# lixie_usb.net
KiCad netlist of a schematic drawn in EAGLE
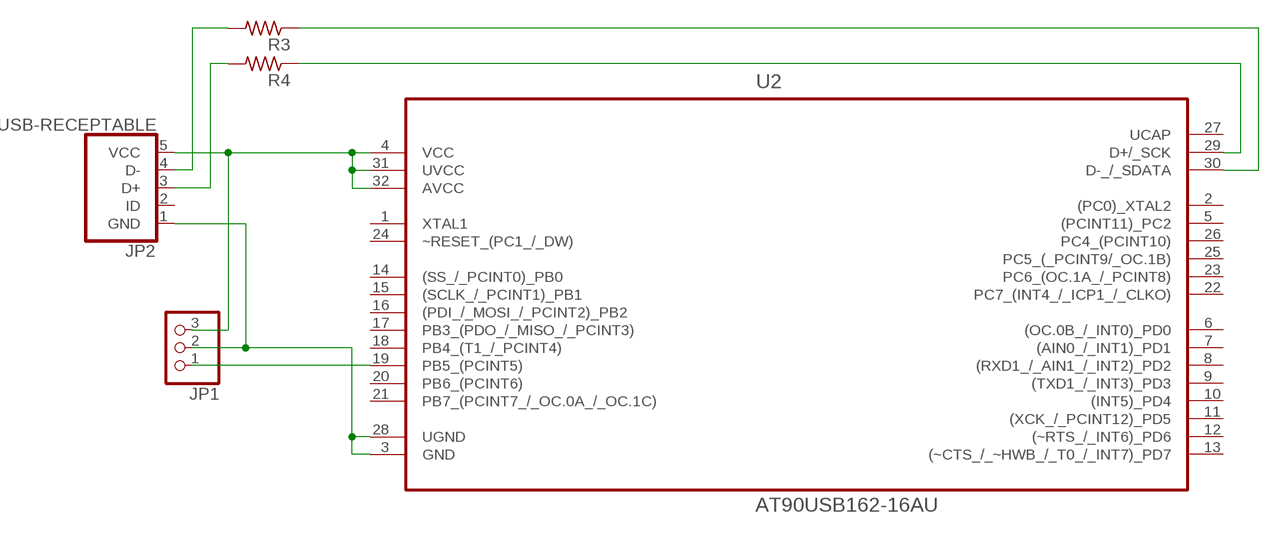
[diagram p0: schematic, sheet 1]

(export (version "E")
  (design (tool "Eeschema 10.0.6"))
  (components
    (comp (ref "JP1")
      (value "PINHD-1X3")
      (footprint "eagle-import:1X03")
      (libsource (lib "eagle-import") (part "PINHD-1X3"))
    )
    (comp (ref "JP2")
      (value "USB-RECEPTABLE")
      (footprint "eagle-import:FCI-10103594-0001LF")
      (libsource (lib "eagle-import") (part "USB-RECEPTABLE"))
    )
    (comp (ref "R3")
      (value "R-US_R0805")
      (footprint "eagle-import:R0805")
      (libsource (lib "eagle-import") (part "R-US_R0805"))
    )
    (comp (ref "R4")
      (value "R-US_R0805")
      (footprint "eagle-import:R0805")
      (libsource (lib "eagle-import") (part "R-US_R0805"))
    )
    (comp (ref "U2")
      (value "AT90USB162-16AU")
      (footprint "eagle-import:QFP80P900X900X120-32N")
      (libsource (lib "eagle-import") (part "AT90USB162-16AU"))
    )
  )
  (nets
    (net (code "1") (name "Net-(JP2-D+)") (class "Default")
      (node (ref "JP2") (pin "3") (pinfunction "D+_3") (pintype "bidirectional"))
      (node (ref "R4") (pin "2") (pinfunction "2_2") (pintype "passive"))
    )
    (net (code "2") (name "Net-(JP2-D-)") (class "Default")
      (node (ref "JP2") (pin "4") (pinfunction "D-_4") (pintype "bidirectional"))
      (node (ref "R3") (pin "2") (pinfunction "2_2") (pintype "passive"))
    )
    (net (code "3") (name "Net-(JP2-GND)") (class "Default")
      (node (ref "JP1") (pin "2") (pinfunction "2_2") (pintype "passive"))
      (node (ref "JP2") (pin "1") (pinfunction "GND_1") (pintype "bidirectional"))
      (node (ref "U2") (pin "28") (pinfunction "UGND_28") (pintype "passive"))
      (node (ref "U2") (pin "3") (pinfunction "GND_3") (pintype "passive"))
    )
    (net (code "4") (name "Net-(JP2-VCC)") (class "Default")
      (node (ref "JP1") (pin "3") (pinfunction "3_3") (pintype "passive"))
      (node (ref "JP2") (pin "5") (pinfunction "VCC_5") (pintype "bidirectional"))
      (node (ref "U2") (pin "31") (pinfunction "UVCC_31") (pintype "power_in"))
      (node (ref "U2") (pin "32") (pinfunction "AVCC_32") (pintype "power_in"))
      (node (ref "U2") (pin "4") (pinfunction "VCC_4") (pintype "power_in"))
    )
    (net (code "5") (name "Net-(U2-D+{slash}_SCK)") (class "Default")
      (node (ref "R4") (pin "1") (pinfunction "1_1") (pintype "passive"))
      (node (ref "U2") (pin "29") (pinfunction "D+/_SCK_29") (pintype "bidirectional"))
    )
    (net (code "6") (name "Net-(U2-D-_{slash}_SDATA)") (class "Default")
      (node (ref "R3") (pin "1") (pinfunction "1_1") (pintype "passive"))
      (node (ref "U2") (pin "30") (pinfunction "D-_/_SDATA_30") (pintype "bidirectional"))
    )
    (net (code "7") (name "Net-(U2-PB5_(PCINT5))") (class "Default")
      (node (ref "JP1") (pin "1") (pinfunction "1_1") (pintype "passive"))
      (node (ref "U2") (pin "19") (pinfunction "PB5_(PCINT5)_19") (pintype "bidirectional"))
    )
    (net (code "8") (name "unconnected-(JP2-ID-Pad2)") (class "Default")
      (node (ref "JP2") (pin "2") (pinfunction "ID_2") (pintype "bidirectional"))
    )
    (net (code "9") (name "unconnected-(U2-(AIN0_{slash}_INT1)_PD1-Pad7)") (class "Default")
      (node (ref "U2") (pin "7") (pinfunction "(AIN0_/_INT1)_PD1_7") (pintype "bidirectional"))
    )
    (net (code "10") (name "unconnected-(U2-(INT5)_PD4-Pad10)") (class "Default")
      (node (ref "U2") (pin "10") (pinfunction "(INT5)_PD4_10") (pintype "bidirectional"))
    )
    (net (code "11") (name "unconnected-(U2-(OC.0B_{slash}_INT0)_PD0-Pad6)") (class "Default")
      (node (ref "U2") (pin "6") (pinfunction "(OC.0B_/_INT0)_PD0_6") (pintype "bidirectional"))
    )
    (net (code "12") (name "unconnected-(U2-(PC0)_XTAL2-Pad2)") (class "Default")
      (node (ref "U2") (pin "2") (pinfunction "(PC0)_XTAL2_2") (pintype "bidirectional"))
    )
    (net (code "13") (name "unconnected-(U2-(PCINT11)_PC2-Pad5)") (class "Default")
      (node (ref "U2") (pin "5") (pinfunction "(PCINT11)_PC2_5") (pintype "bidirectional"))
    )
    (net (code "14") (name "unconnected-(U2-(PDI_{slash}_MOSI_{slash}_PCINT2)_PB2-Pad16)") (class "Default")
      (node (ref "U2") (pin "16") (pinfunction "(PDI_/_MOSI_/_PCINT2)_PB2_16") (pintype "bidirectional"))
    )
    (net (code "15") (name "unconnected-(U2-(RXD1_{slash}_AIN1_{slash}_INT2)_PD2-Pad8)") (class "Default")
      (node (ref "U2") (pin "8") (pinfunction "(RXD1_/_AIN1_/_INT2)_PD2_8") (pintype "bidirectional"))
    )
    (net (code "16") (name "unconnected-(U2-(SCLK_{slash}_PCINT1)_PB1-Pad15)") (class "Default")
      (node (ref "U2") (pin "15") (pinfunction "(SCLK_/_PCINT1)_PB1_15") (pintype "bidirectional"))
    )
    (net (code "17") (name "unconnected-(U2-(SS_{slash}_PCINT0)_PB0-Pad14)") (class "Default")
      (node (ref "U2") (pin "14") (pinfunction "(SS_/_PCINT0)_PB0_14") (pintype "bidirectional"))
    )
    (net (code "18") (name "unconnected-(U2-(TXD1_{slash}_INT3)_PD3-Pad9)") (class "Default")
      (node (ref "U2") (pin "9") (pinfunction "(TXD1_/_INT3)_PD3_9") (pintype "bidirectional"))
    )
    (net (code "19") (name "unconnected-(U2-(XCK_{slash}_PCINT12)_PD5-Pad11)") (class "Default")
      (node (ref "U2") (pin "11") (pinfunction "(XCK_/_PCINT12)_PD5_11") (pintype "bidirectional"))
    )
    (net (code "20") (name "unconnected-(U2-(~{CTS_{slash}_}HWB_{slash}_T0_{slash}_INT7)_PD7-Pad13)") (class "Default")
      (node (ref "U2") (pin "13") (pinfunction "(~{CTS_/_}HWB_/_T0_/_INT7)_PD7_13") (pintype "bidirectional"))
    )
    (net (code "21") (name "unconnected-(U2-(~{RTS_{slash}_INT6})_PD6-Pad12)") (class "Default")
      (node (ref "U2") (pin "12") (pinfunction "(~{RTS_/_INT6})_PD6_12") (pintype "bidirectional"))
    )
    (net (code "22") (name "unconnected-(U2-PB3_(PDO_{slash}_MISO_{slash}_PCINT3)-Pad17)") (class "Default")
      (node (ref "U2") (pin "17") (pinfunction "PB3_(PDO_/_MISO_/_PCINT3)_17") (pintype "bidirectional"))
    )
    (net (code "23") (name "unconnected-(U2-PB4_(T1_{slash}_PCINT4)-Pad18)") (class "Default")
      (node (ref "U2") (pin "18") (pinfunction "PB4_(T1_/_PCINT4)_18") (pintype "bidirectional"))
    )
    (net (code "24") (name "unconnected-(U2-PB6_(PCINT6)-Pad20)") (class "Default")
      (node (ref "U2") (pin "20") (pinfunction "PB6_(PCINT6)_20") (pintype "bidirectional"))
    )
    (net (code "25") (name "unconnected-(U2-PB7_(PCINT7_{slash}_OC.0A_{slash}_OC.1C)-Pad21)") (class "Default")
      (node (ref "U2") (pin "21") (pinfunction "PB7_(PCINT7_/_OC.0A_/_OC.1C)_21") (pintype "bidirectional"))
    )
    (net (code "26") (name "unconnected-(U2-PC4_(PCINT10)-Pad26)") (class "Default")
      (node (ref "U2") (pin "26") (pinfunction "PC4_(PCINT10)_26") (pintype "bidirectional"))
    )
    (net (code "27") (name "unconnected-(U2-PC5_(_PCINT9{slash}_OC.1B)-Pad25)") (class "Default")
      (node (ref "U2") (pin "25") (pinfunction "PC5_(_PCINT9/_OC.1B)_25") (pintype "bidirectional"))
    )
    (net (code "28") (name "unconnected-(U2-PC6_(OC.1A_{slash}_PCINT8)-Pad23)") (class "Default")
      (node (ref "U2") (pin "23") (pinfunction "PC6_(OC.1A_/_PCINT8)_23") (pintype "bidirectional"))
    )
    (net (code "29") (name "unconnected-(U2-PC7_(INT4_{slash}_ICP1_{slash}_CLKO)-Pad22)") (class "Default")
      (node (ref "U2") (pin "22") (pinfunction "PC7_(INT4_/_ICP1_/_CLKO)_22") (pintype "bidirectional"))
    )
    (net (code "30") (name "unconnected-(U2-UCAP-Pad27)") (class "Default")
      (node (ref "U2") (pin "27") (pinfunction "UCAP_27") (pintype "output"))
    )
    (net (code "31") (name "unconnected-(U2-XTAL1-Pad1)") (class "Default")
      (node (ref "U2") (pin "1") (pinfunction "XTAL1_1") (pintype "input"))
    )
    (net (code "32") (name "unconnected-(U2-~{RESET_(PC1_{slash}_DW})-Pad24)") (class "Default")
      (node (ref "U2") (pin "24") (pinfunction "~{RESET_(PC1_/_DW})_24") (pintype "bidirectional"))
    )
  )
)
